# main.net
KiCad netlist of a schematic drawn in Altium Designer
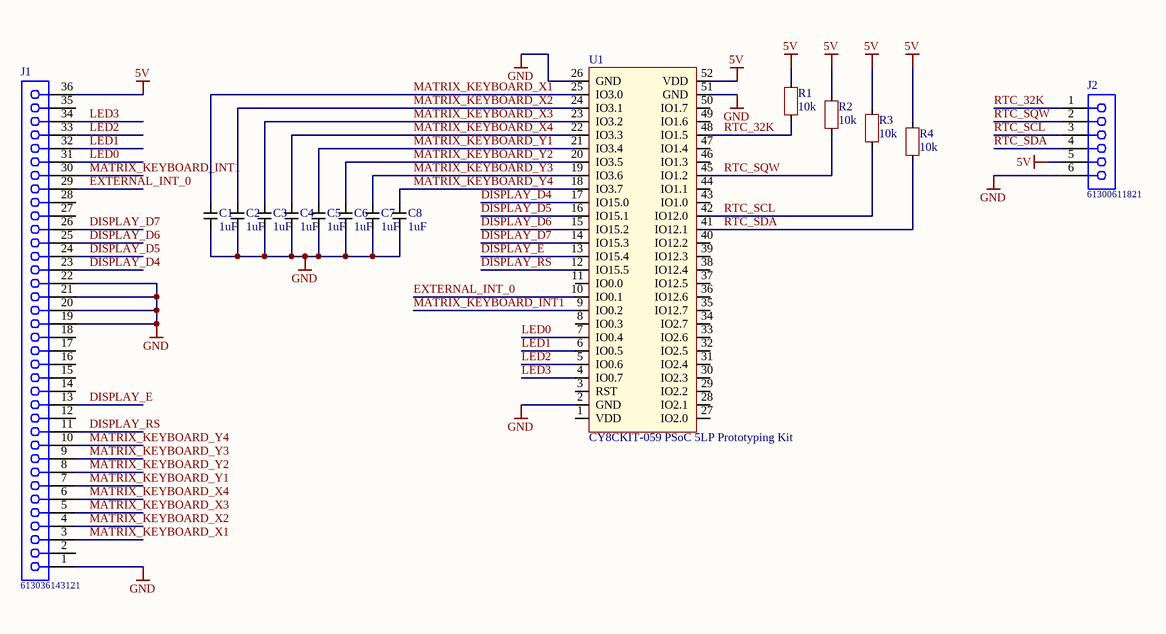
[diagram p0: main.SchDoc]

(export (version "E")
  (design (tool "Eeschema 10.0.6"))
  (components
    (comp (ref "C1")
      (value "1uF")
      (footprint "C1206_DEVELOPMENT")
      (description "SMD Multilayer Ceramic Capacitor, 1 µF, 16 V, 1206 [3216 Metric], +80%, -20%, Y5V, C Series KEMET")
      (libsource (lib "Capacitors") (part "1uF,1206"))
    )
    (comp (ref "C2")
      (value "1uF")
      (footprint "C1206_DEVELOPMENT")
      (description "SMD Multilayer Ceramic Capacitor, 1 µF, 16 V, 1206 [3216 Metric], +80%, -20%, Y5V, C Series KEMET")
      (libsource (lib "Capacitors") (part "1uF,1206"))
    )
    (comp (ref "C3")
      (value "1uF")
      (footprint "C1206_DEVELOPMENT")
      (description "SMD Multilayer Ceramic Capacitor, 1 µF, 16 V, 1206 [3216 Metric], +80%, -20%, Y5V, C Series KEMET")
      (libsource (lib "Capacitors") (part "1uF,1206"))
    )
    (comp (ref "C4")
      (value "1uF")
      (footprint "C1206_DEVELOPMENT")
      (description "SMD Multilayer Ceramic Capacitor, 1 µF, 16 V, 1206 [3216 Metric], +80%, -20%, Y5V, C Series KEMET")
      (libsource (lib "Capacitors") (part "1uF,1206"))
    )
    (comp (ref "C5")
      (value "1uF")
      (footprint "C1206_DEVELOPMENT")
      (description "SMD Multilayer Ceramic Capacitor, 1 µF, 16 V, 1206 [3216 Metric], +80%, -20%, Y5V, C Series KEMET")
      (libsource (lib "Capacitors") (part "1uF,1206"))
    )
    (comp (ref "C6")
      (value "1uF")
      (footprint "C1206_DEVELOPMENT")
      (description "SMD Multilayer Ceramic Capacitor, 1 µF, 16 V, 1206 [3216 Metric], +80%, -20%, Y5V, C Series KEMET")
      (libsource (lib "Capacitors") (part "1uF,1206"))
    )
    (comp (ref "C7")
      (value "1uF")
      (footprint "C1206_DEVELOPMENT")
      (description "SMD Multilayer Ceramic Capacitor, 1 µF, 16 V, 1206 [3216 Metric], +80%, -20%, Y5V, C Series KEMET")
      (libsource (lib "Capacitors") (part "1uF,1206"))
    )
    (comp (ref "C8")
      (value "1uF")
      (footprint "C1206_DEVELOPMENT")
      (description "SMD Multilayer Ceramic Capacitor, 1 µF, 16 V, 1206 [3216 Metric], +80%, -20%, Y5V, C Series KEMET")
      (libsource (lib "Capacitors") (part "1uF,1206"))
    )
    (comp (ref "J1")
      (value "613036143121")
      (footprint "613036143121")
      (libsource (lib "Connectoren") (part "613036143121"))
    )
    (comp (ref "J2")
      (value "61300611821")
      (footprint "61300611821")
      (description "THT Vertical Socket Header WR-PHD, Pitch 2.54 mm, Single Row, 6 pins")
      (libsource (lib "Connectoren") (part "61300611821"))
    )
    (comp (ref "R1")
      (value "10k")
      (footprint "R1206_DEVELOPMENT")
      (description "10k, 1206, 250mW, 200V")
      (fields (field (name "POWER") "250mW"))
      (libsource (lib "Resistors") (part "10k, 1206"))
    )
    (comp (ref "R2")
      (value "10k")
      (footprint "R1206_DEVELOPMENT")
      (description "10k, 1206, 250mW, 200V")
      (fields (field (name "POWER") "250mW"))
      (libsource (lib "Resistors") (part "10k, 1206"))
    )
    (comp (ref "R3")
      (value "10k")
      (footprint "R1206_DEVELOPMENT")
      (description "10k, 1206, 250mW, 200V")
      (fields (field (name "POWER") "250mW"))
      (libsource (lib "Resistors") (part "10k, 1206"))
    )
    (comp (ref "R4")
      (value "10k")
      (footprint "R1206_DEVELOPMENT")
      (description "10k, 1206, 250mW, 200V")
      (fields (field (name "POWER") "250mW"))
      (libsource (lib "Resistors") (part "10k, 1206"))
    )
    (comp (ref "U1")
      (value "CY8CKIT-059 PSoC 5LP Prototyping Kit")
      (footprint "CY8CKIT-059-5LP")
      (libsource (lib "Development_Boards") (part "CY8CKIT-059 PSoC 5LP Prototyping Kit"))
    )
  )
  (nets
    (net (code "1") (name "/DISPLAY_D4") (class "Default")
      (node (ref "J1") (pin "23") (pinfunction "0_23") (pintype "passive"))
      (node (ref "U1") (pin "17") (pinfunction "IO15.0_17") (pintype "passive"))
    )
    (net (code "2") (name "/DISPLAY_D5") (class "Default")
      (node (ref "J1") (pin "24") (pinfunction "0_24") (pintype "passive"))
      (node (ref "U1") (pin "16") (pinfunction "IO15.1_16") (pintype "passive"))
    )
    (net (code "3") (name "/DISPLAY_D6") (class "Default")
      (node (ref "J1") (pin "25") (pinfunction "0_25") (pintype "passive"))
      (node (ref "U1") (pin "15") (pinfunction "IO15.2_15") (pintype "passive"))
    )
    (net (code "4") (name "/DISPLAY_D7") (class "Default")
      (node (ref "J1") (pin "26") (pinfunction "0_26") (pintype "passive"))
      (node (ref "U1") (pin "14") (pinfunction "IO15.3_14") (pintype "passive"))
    )
    (net (code "5") (name "/DISPLAY_E") (class "Default")
      (node (ref "J1") (pin "13") (pinfunction "13_13") (pintype "passive"))
      (node (ref "U1") (pin "13") (pinfunction "IO15.4_13") (pintype "passive"))
    )
    (net (code "6") (name "/DISPLAY_RS") (class "Default")
      (node (ref "J1") (pin "11") (pinfunction "11_11") (pintype "passive"))
      (node (ref "U1") (pin "12") (pinfunction "IO15.5_12") (pintype "passive"))
    )
    (net (code "7") (name "/EXTERNAL_INT_0") (class "Default")
      (node (ref "J1") (pin "29") (pinfunction "0_29") (pintype "passive"))
      (node (ref "U1") (pin "10") (pinfunction "IO0.1_10") (pintype "passive"))
    )
    (net (code "8") (name "/LED0") (class "Default")
      (node (ref "J1") (pin "31") (pinfunction "0_31") (pintype "passive"))
      (node (ref "U1") (pin "7") (pinfunction "IO0.4_7") (pintype "passive"))
    )
    (net (code "9") (name "/LED1") (class "Default")
      (node (ref "J1") (pin "32") (pinfunction "0_32") (pintype "passive"))
      (node (ref "U1") (pin "6") (pinfunction "IO0.5_6") (pintype "passive"))
    )
    (net (code "10") (name "/LED2") (class "Default")
      (node (ref "J1") (pin "33") (pinfunction "0_33") (pintype "passive"))
      (node (ref "U1") (pin "5") (pinfunction "IO0.6_5") (pintype "passive"))
    )
    (net (code "11") (name "/LED3") (class "Default")
      (node (ref "J1") (pin "34") (pinfunction "0_34") (pintype "passive"))
      (node (ref "U1") (pin "4") (pinfunction "IO0.7_4") (pintype "passive"))
    )
    (net (code "12") (name "/MATRIX_KEYBOARD_INT1") (class "Default")
      (node (ref "J1") (pin "30") (pinfunction "0_30") (pintype "passive"))
      (node (ref "U1") (pin "9") (pinfunction "IO0.2_9") (pintype "passive"))
    )
    (net (code "13") (name "/MATRIX_KEYBOARD_X1") (class "Default")
      (node (ref "C1") (pin "2") (pinfunction "2_2") (pintype "passive"))
      (node (ref "J1") (pin "3") (pinfunction "3_3") (pintype "passive"))
      (node (ref "U1") (pin "25") (pinfunction "IO3.0_25") (pintype "passive"))
    )
    (net (code "14") (name "/MATRIX_KEYBOARD_X2") (class "Default")
      (node (ref "C2") (pin "2") (pinfunction "2_2") (pintype "passive"))
      (node (ref "J1") (pin "4") (pinfunction "4_4") (pintype "passive"))
      (node (ref "U1") (pin "24") (pinfunction "IO3.1_24") (pintype "passive"))
    )
    (net (code "15") (name "/MATRIX_KEYBOARD_X3") (class "Default")
      (node (ref "C3") (pin "2") (pinfunction "2_2") (pintype "passive"))
      (node (ref "J1") (pin "5") (pinfunction "5_5") (pintype "passive"))
      (node (ref "U1") (pin "23") (pinfunction "IO3.2_23") (pintype "passive"))
    )
    (net (code "16") (name "/MATRIX_KEYBOARD_X4") (class "Default")
      (node (ref "C4") (pin "2") (pinfunction "2_2") (pintype "passive"))
      (node (ref "J1") (pin "6") (pinfunction "6_6") (pintype "passive"))
      (node (ref "U1") (pin "22") (pinfunction "IO3.3_22") (pintype "passive"))
    )
    (net (code "17") (name "/MATRIX_KEYBOARD_Y1") (class "Default")
      (node (ref "C5") (pin "2") (pinfunction "2_2") (pintype "passive"))
      (node (ref "J1") (pin "7") (pinfunction "7_7") (pintype "passive"))
      (node (ref "U1") (pin "21") (pinfunction "IO3.4_21") (pintype "passive"))
    )
    (net (code "18") (name "/MATRIX_KEYBOARD_Y2") (class "Default")
      (node (ref "C6") (pin "2") (pinfunction "2_2") (pintype "passive"))
      (node (ref "J1") (pin "8") (pinfunction "8_8") (pintype "passive"))
      (node (ref "U1") (pin "20") (pinfunction "IO3.5_20") (pintype "passive"))
    )
    (net (code "19") (name "/MATRIX_KEYBOARD_Y3") (class "Default")
      (node (ref "C7") (pin "2") (pinfunction "2_2") (pintype "passive"))
      (node (ref "J1") (pin "9") (pinfunction "9_9") (pintype "passive"))
      (node (ref "U1") (pin "19") (pinfunction "IO3.6_19") (pintype "passive"))
    )
    (net (code "20") (name "/MATRIX_KEYBOARD_Y4") (class "Default")
      (node (ref "C8") (pin "2") (pinfunction "2_2") (pintype "passive"))
      (node (ref "J1") (pin "10") (pinfunction "10_10") (pintype "passive"))
      (node (ref "U1") (pin "18") (pinfunction "IO3.7_18") (pintype "passive"))
    )
    (net (code "21") (name "/RTC_32K") (class "Default")
      (node (ref "J2") (pin "1") (pinfunction "1_1") (pintype "passive"))
      (node (ref "R1") (pin "1") (pinfunction "1_1") (pintype "passive"))
      (node (ref "U1") (pin "48") (pinfunction "IO1.5_48") (pintype "passive"))
    )
    (net (code "22") (name "/RTC_SCL") (class "Default")
      (node (ref "J2") (pin "3") (pinfunction "3_3") (pintype "passive"))
      (node (ref "R3") (pin "1") (pinfunction "1_1") (pintype "passive"))
      (node (ref "U1") (pin "42") (pinfunction "IO12.0_42") (pintype "passive"))
    )
    (net (code "23") (name "/RTC_SDA") (class "Default")
      (node (ref "J2") (pin "4") (pinfunction "4_4") (pintype "passive"))
      (node (ref "R4") (pin "1") (pinfunction "1_1") (pintype "passive"))
      (node (ref "U1") (pin "41") (pinfunction "IO12.1_41") (pintype "passive"))
    )
    (net (code "24") (name "/RTC_SQW") (class "Default")
      (node (ref "J2") (pin "2") (pinfunction "2_2") (pintype "passive"))
      (node (ref "R2") (pin "1") (pinfunction "1_1") (pintype "passive"))
      (node (ref "U1") (pin "45") (pinfunction "IO1.2_45") (pintype "passive"))
    )
    (net (code "25") (name "5V") (class "Default")
      (node (ref "J1") (pin "36") (pinfunction "0_36") (pintype "passive"))
      (node (ref "J2") (pin "5") (pinfunction "5_5") (pintype "passive"))
      (node (ref "R1") (pin "2") (pinfunction "2_2") (pintype "passive"))
      (node (ref "R2") (pin "2") (pinfunction "2_2") (pintype "passive"))
      (node (ref "R3") (pin "2") (pinfunction "2_2") (pintype "passive"))
      (node (ref "R4") (pin "2") (pinfunction "2_2") (pintype "passive"))
      (node (ref "U1") (pin "52") (pinfunction "VDD_52") (pintype "passive"))
    )
    (net (code "26") (name "GND") (class "Default")
      (node (ref "C1") (pin "1") (pinfunction "1_1") (pintype "passive"))
      (node (ref "C2") (pin "1") (pinfunction "1_1") (pintype "passive"))
      (node (ref "C3") (pin "1") (pinfunction "1_1") (pintype "passive"))
      (node (ref "C4") (pin "1") (pinfunction "1_1") (pintype "passive"))
      (node (ref "C5") (pin "1") (pinfunction "1_1") (pintype "passive"))
      (node (ref "C6") (pin "1") (pinfunction "1_1") (pintype "passive"))
      (node (ref "C7") (pin "1") (pinfunction "1_1") (pintype "passive"))
      (node (ref "C8") (pin "1") (pinfunction "1_1") (pintype "passive"))
      (node (ref "J1") (pin "1") (pinfunction "1_1") (pintype "passive"))
      (node (ref "J1") (pin "19") (pinfunction "0_19") (pintype "passive"))
      (node (ref "J1") (pin "20") (pinfunction "0_20") (pintype "passive"))
      (node (ref "J1") (pin "21") (pinfunction "0_21") (pintype "passive"))
      (node (ref "J1") (pin "22") (pinfunction "0_22") (pintype "passive"))
      (node (ref "J2") (pin "6") (pinfunction "6_6") (pintype "passive"))
      (node (ref "U1") (pin "2") (pinfunction "GND_2") (pintype "passive"))
      (node (ref "U1") (pin "26") (pinfunction "GND_26") (pintype "passive"))
      (node (ref "U1") (pin "51") (pinfunction "GND_51") (pintype "passive"))
    )
    (net (code "27") (name "unconnected-(J1-0-Pad17)") (class "Default")
      (node (ref "J1") (pin "17") (pinfunction "0_17") (pintype "passive"))
    )
    (net (code "28") (name "unconnected-(J1-0-Pad18)") (class "Default")
      (node (ref "J1") (pin "18") (pinfunction "0_18") (pintype "passive"))
    )
    (net (code "29") (name "unconnected-(J1-0-Pad27)") (class "Default")
      (node (ref "J1") (pin "27") (pinfunction "0_27") (pintype "passive"))
    )
    (net (code "30") (name "unconnected-(J1-0-Pad28)") (class "Default")
      (node (ref "J1") (pin "28") (pinfunction "0_28") (pintype "passive"))
    )
    (net (code "31") (name "unconnected-(J1-0-Pad35)") (class "Default")
      (node (ref "J1") (pin "35") (pinfunction "0_35") (pintype "passive"))
    )
    (net (code "32") (name "unconnected-(J1-Pad2)") (class "Default")
      (node (ref "J1") (pin "2") (pinfunction "2_2") (pintype "passive"))
    )
    (net (code "33") (name "unconnected-(J1-Pad12)") (class "Default")
      (node (ref "J1") (pin "12") (pinfunction "12_12") (pintype "passive"))
    )
    (net (code "34") (name "unconnected-(J1-Pad14)") (class "Default")
      (node (ref "J1") (pin "14") (pinfunction "14_14") (pintype "passive"))
    )
    (net (code "35") (name "unconnected-(J1-Pad15)") (class "Default")
      (node (ref "J1") (pin "15") (pinfunction "15_15") (pintype "passive"))
    )
    (net (code "36") (name "unconnected-(J1-Pad16)") (class "Default")
      (node (ref "J1") (pin "16") (pinfunction "16_16") (pintype "passive"))
    )
    (net (code "37") (name "unconnected-(U1-IO0.0-Pad11)") (class "Default")
      (node (ref "U1") (pin "11") (pinfunction "IO0.0_11") (pintype "passive"))
    )
    (net (code "38") (name "unconnected-(U1-IO0.3-Pad8)") (class "Default")
      (node (ref "U1") (pin "8") (pinfunction "IO0.3_8") (pintype "passive"))
    )
    (net (code "39") (name "unconnected-(U1-IO1.0-Pad43)") (class "Default")
      (node (ref "U1") (pin "43") (pinfunction "IO1.0_43") (pintype "passive"))
    )
    (net (code "40") (name "unconnected-(U1-IO1.1-Pad44)") (class "Default")
      (node (ref "U1") (pin "44") (pinfunction "IO1.1_44") (pintype "passive"))
    )
    (net (code "41") (name "unconnected-(U1-IO1.3-Pad46)") (class "Default")
      (node (ref "U1") (pin "46") (pinfunction "IO1.3_46") (pintype "passive"))
    )
    (net (code "42") (name "unconnected-(U1-IO1.4-Pad47)") (class "Default")
      (node (ref "U1") (pin "47") (pinfunction "IO1.4_47") (pintype "passive"))
    )
    (net (code "43") (name "unconnected-(U1-IO1.6-Pad49)") (class "Default")
      (node (ref "U1") (pin "49") (pinfunction "IO1.6_49") (pintype "passive"))
    )
    (net (code "44") (name "unconnected-(U1-IO1.7-Pad50)") (class "Default")
      (node (ref "U1") (pin "50") (pinfunction "IO1.7_50") (pintype "passive"))
    )
    (net (code "45") (name "unconnected-(U1-IO2.0-Pad27)") (class "Default")
      (node (ref "U1") (pin "27") (pinfunction "IO2.0_27") (pintype "passive"))
    )
    (net (code "46") (name "unconnected-(U1-IO2.1-Pad28)") (class "Default")
      (node (ref "U1") (pin "28") (pinfunction "IO2.1_28") (pintype "passive"))
    )
    (net (code "47") (name "unconnected-(U1-IO2.2-Pad29)") (class "Default")
      (node (ref "U1") (pin "29") (pinfunction "IO2.2_29") (pintype "passive"))
    )
    (net (code "48") (name "unconnected-(U1-IO2.3-Pad30)") (class "Default")
      (node (ref "U1") (pin "30") (pinfunction "IO2.3_30") (pintype "passive"))
    )
    (net (code "49") (name "unconnected-(U1-IO2.4-Pad31)") (class "Default")
      (node (ref "U1") (pin "31") (pinfunction "IO2.4_31") (pintype "passive"))
    )
    (net (code "50") (name "unconnected-(U1-IO2.5-Pad32)") (class "Default")
      (node (ref "U1") (pin "32") (pinfunction "IO2.5_32") (pintype "passive"))
    )
    (net (code "51") (name "unconnected-(U1-IO2.6-Pad33)") (class "Default")
      (node (ref "U1") (pin "33") (pinfunction "IO2.6_33") (pintype "passive"))
    )
    (net (code "52") (name "unconnected-(U1-IO2.7-Pad34)") (class "Default")
      (node (ref "U1") (pin "34") (pinfunction "IO2.7_34") (pintype "passive"))
    )
    (net (code "53") (name "unconnected-(U1-IO12.2-Pad40)") (class "Default")
      (node (ref "U1") (pin "40") (pinfunction "IO12.2_40") (pintype "passive"))
    )
    (net (code "54") (name "unconnected-(U1-IO12.3-Pad39)") (class "Default")
      (node (ref "U1") (pin "39") (pinfunction "IO12.3_39") (pintype "passive"))
    )
    (net (code "55") (name "unconnected-(U1-IO12.4-Pad38)") (class "Default")
      (node (ref "U1") (pin "38") (pinfunction "IO12.4_38") (pintype "passive"))
    )
    (net (code "56") (name "unconnected-(U1-IO12.5-Pad37)") (class "Default")
      (node (ref "U1") (pin "37") (pinfunction "IO12.5_37") (pintype "passive"))
    )
    (net (code "57") (name "unconnected-(U1-IO12.6-Pad36)") (class "Default")
      (node (ref "U1") (pin "36") (pinfunction "IO12.6_36") (pintype "passive"))
    )
    (net (code "58") (name "unconnected-(U1-IO12.7-Pad35)") (class "Default")
      (node (ref "U1") (pin "35") (pinfunction "IO12.7_35") (pintype "passive"))
    )
    (net (code "59") (name "unconnected-(U1-RST-Pad3)") (class "Default")
      (node (ref "U1") (pin "3") (pinfunction "RST_3") (pintype "passive"))
    )
    (net (code "60") (name "unconnected-(U1-VDD-Pad1)") (class "Default")
      (node (ref "U1") (pin "1") (pinfunction "VDD_1") (pintype "passive"))
    )
  )
)
